# ax.net
KiCad netlist of a schematic drawn in EAGLE
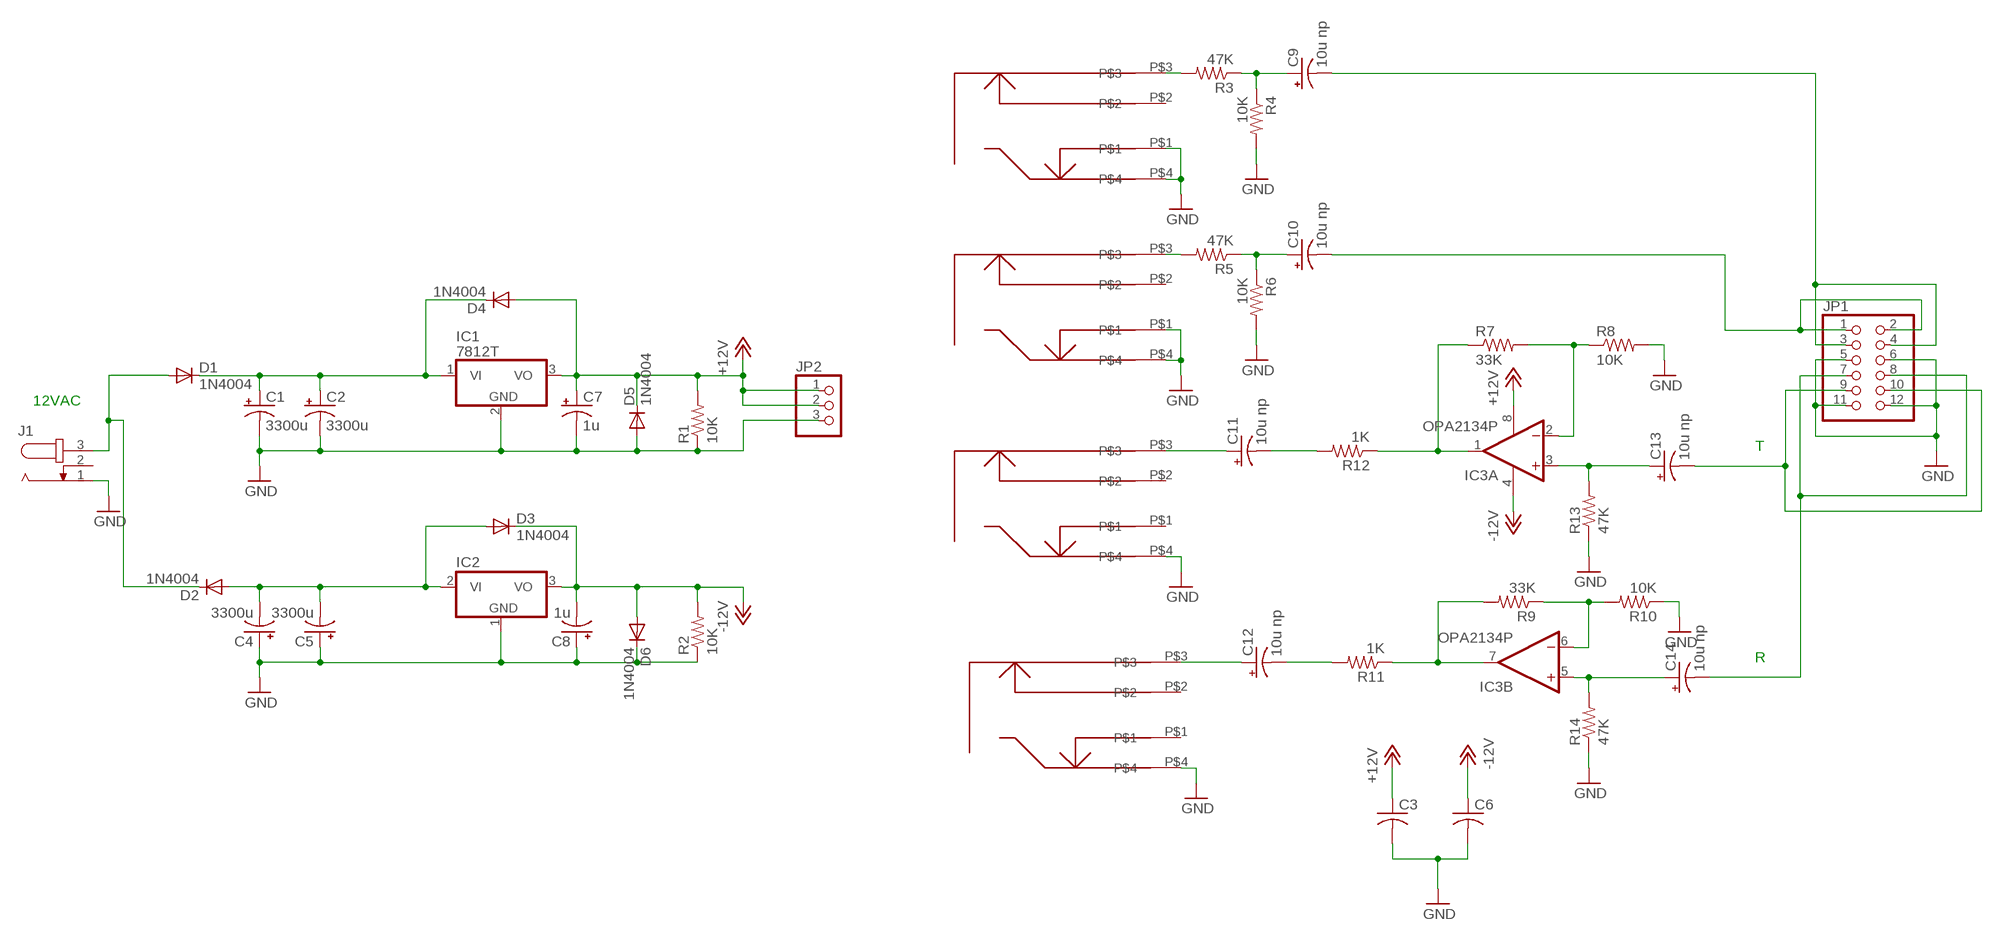
[diagram p0: schematic, sheet 1]

(export (version "E")
  (design (tool "Eeschema 10.0.6"))
  (components
    (comp (ref "C1")
      (value "3300u")
      (footprint "eagle-import:E7,5-18")
      (libsource (lib "eagle-import") (part "CPOL-USE7.5-18"))
    )
    (comp (ref "C2")
      (value "3300u")
      (footprint "eagle-import:E7,5-18")
      (libsource (lib "eagle-import") (part "CPOL-USE7.5-18"))
    )
    (comp (ref "C3")
      (value "C-US050-030X075")
      (footprint "eagle-import:C050-030X075")
      (libsource (lib "eagle-import") (part "C-US050-030X075"))
    )
    (comp (ref "C4")
      (value "3300u")
      (footprint "eagle-import:E7,5-18")
      (libsource (lib "eagle-import") (part "CPOL-USE7.5-18"))
    )
    (comp (ref "C5")
      (value "3300u")
      (footprint "eagle-import:E7,5-18")
      (libsource (lib "eagle-import") (part "CPOL-USE7.5-18"))
    )
    (comp (ref "C6")
      (value "C-US050-030X075")
      (footprint "eagle-import:C050-030X075")
      (libsource (lib "eagle-import") (part "C-US050-030X075"))
    )
    (comp (ref "C7")
      (value "1u")
      (footprint "eagle-import:E2-5")
      (libsource (lib "eagle-import") (part "CPOL-USE2-5"))
    )
    (comp (ref "C8")
      (value "1u")
      (footprint "eagle-import:E2-5")
      (libsource (lib "eagle-import") (part "CPOL-USE2-5"))
    )
    (comp (ref "C9")
      (value "10u np")
      (footprint "eagle-import:E2-5")
      (libsource (lib "eagle-import") (part "CPOL-USE2-5"))
    )
    (comp (ref "C10")
      (value "10u np")
      (footprint "eagle-import:E2-5")
      (libsource (lib "eagle-import") (part "CPOL-USE2-5"))
    )
    (comp (ref "C11")
      (value "10u np")
      (footprint "eagle-import:E2-5")
      (libsource (lib "eagle-import") (part "CPOL-USE2-5"))
    )
    (comp (ref "C12")
      (value "10u np")
      (footprint "eagle-import:E2-5")
      (libsource (lib "eagle-import") (part "CPOL-USE2-5"))
    )
    (comp (ref "C13")
      (value "10u np")
      (footprint "eagle-import:E2-5")
      (libsource (lib "eagle-import") (part "CPOL-USE2-5"))
    )
    (comp (ref "C14")
      (value "10u np")
      (footprint "eagle-import:E2-5")
      (libsource (lib "eagle-import") (part "CPOL-USE2-5"))
    )
    (comp (ref "D1")
      (value "1N4004")
      (footprint "eagle-import:DO41-10")
      (libsource (lib "eagle-import") (part "1N4004"))
    )
    (comp (ref "D2")
      (value "1N4004")
      (footprint "eagle-import:DO41-10")
      (libsource (lib "eagle-import") (part "1N4004"))
    )
    (comp (ref "D3")
      (value "1N4004")
      (footprint "eagle-import:DO41-10")
      (libsource (lib "eagle-import") (part "1N4004"))
    )
    (comp (ref "D4")
      (value "1N4004")
      (footprint "eagle-import:DO41-10")
      (libsource (lib "eagle-import") (part "1N4004"))
    )
    (comp (ref "D5")
      (value "1N4004")
      (footprint "eagle-import:DO41-10")
      (libsource (lib "eagle-import") (part "1N4004"))
    )
    (comp (ref "D6")
      (value "1N4004")
      (footprint "eagle-import:DO41-10")
      (libsource (lib "eagle-import") (part "1N4004"))
    )
    (comp (ref "IC1")
      (value "7812T")
      (footprint "eagle-import:TO220H")
      (libsource (lib "eagle-import") (part "78T12"))
    )
    (comp (ref "IC2")
      (value "7906T")
      (footprint "eagle-import:TO220H")
      (libsource (lib "eagle-import") (part "79T06"))
    )
    (comp (ref "IC3")
      (value "OPA2134P")
      (footprint "eagle-import:DIL08")
      (libsource (lib "eagle-import") (part "OPA2134P"))
    )
    (comp (ref "INL")
      (value "NMJ4HCD2")
      (footprint "eagle-import:NMJ4HCD2")
      (libsource (lib "eagle-import") (part "NMJ4HCD2"))
    )
    (comp (ref "INR")
      (value "NMJ4HCD2")
      (footprint "eagle-import:NMJ4HCD2")
      (libsource (lib "eagle-import") (part "NMJ4HCD2"))
    )
    (comp (ref "J1")
      (value "JACK-PLUG0")
      (footprint "eagle-import:SPC4077")
      (libsource (lib "eagle-import") (part "JACK-PLUG0"))
    )
    (comp (ref "JP1")
      (value "PINHD-2X6")
      (footprint "eagle-import:2X06")
      (libsource (lib "eagle-import") (part "PINHD-2X6"))
    )
    (comp (ref "JP2")
      (value "PINHD-1X3")
      (footprint "eagle-import:1X03")
      (libsource (lib "eagle-import") (part "PINHD-1X3"))
    )
    (comp (ref "OUTL")
      (value "NMJ4HCD2")
      (footprint "eagle-import:NMJ4HCD2")
      (libsource (lib "eagle-import") (part "NMJ4HCD2"))
    )
    (comp (ref "OUTR")
      (value "NMJ4HCD2")
      (footprint "eagle-import:NMJ4HCD2")
      (libsource (lib "eagle-import") (part "NMJ4HCD2"))
    )
    (comp (ref "R1")
      (value "10K")
      (footprint "eagle-import:0207_7")
      (libsource (lib "eagle-import") (part "R-US_0207/7"))
    )
    (comp (ref "R2")
      (value "10K")
      (footprint "eagle-import:0207_7")
      (libsource (lib "eagle-import") (part "R-US_0207/7"))
    )
    (comp (ref "R3")
      (value "47K")
      (footprint "eagle-import:0207_7")
      (libsource (lib "eagle-import") (part "R-US_0207/7"))
    )
    (comp (ref "R4")
      (value "10K")
      (footprint "eagle-import:0207_7")
      (libsource (lib "eagle-import") (part "R-US_0207/7"))
    )
    (comp (ref "R5")
      (value "47K")
      (footprint "eagle-import:0207_7")
      (libsource (lib "eagle-import") (part "R-US_0207/7"))
    )
    (comp (ref "R6")
      (value "10K")
      (footprint "eagle-import:0207_7")
      (libsource (lib "eagle-import") (part "R-US_0207/7"))
    )
    (comp (ref "R7")
      (value "33K")
      (footprint "eagle-import:0207_7")
      (libsource (lib "eagle-import") (part "R-US_0207/7"))
    )
    (comp (ref "R8")
      (value "10K")
      (footprint "eagle-import:0207_7")
      (libsource (lib "eagle-import") (part "R-US_0207/7"))
    )
    (comp (ref "R9")
      (value "33K")
      (footprint "eagle-import:0207_7")
      (libsource (lib "eagle-import") (part "R-US_0207/7"))
    )
    (comp (ref "R10")
      (value "10K")
      (footprint "eagle-import:0207_7")
      (libsource (lib "eagle-import") (part "R-US_0207/7"))
    )
    (comp (ref "R11")
      (value "1K")
      (footprint "eagle-import:0207_7")
      (libsource (lib "eagle-import") (part "R-US_0207/7"))
    )
    (comp (ref "R12")
      (value "1K")
      (footprint "eagle-import:0207_7")
      (libsource (lib "eagle-import") (part "R-US_0207/7"))
    )
    (comp (ref "R13")
      (value "47K")
      (footprint "eagle-import:0207_7")
      (libsource (lib "eagle-import") (part "R-US_0207/7"))
    )
    (comp (ref "R14")
      (value "47K")
      (footprint "eagle-import:0207_7")
      (libsource (lib "eagle-import") (part "R-US_0207/7"))
    )
  )
  (nets
    (net (code "1") (name "+12V") (class "Default")
      (node (ref "C3") (pin "1") (pinfunction "1_1") (pintype "passive"))
      (node (ref "C7") (pin "+") (pinfunction "+_+") (pintype "passive"))
      (node (ref "D4") (pin "A") (pinfunction "A_A") (pintype "passive"))
      (node (ref "D5") (pin "C") (pinfunction "C_C") (pintype "passive"))
      (node (ref "IC1") (pin "3") (pinfunction "VO_3") (pintype "passive"))
      (node (ref "IC3") (pin "8") (pinfunction "V+_8") (pintype "power_in"))
      (node (ref "JP2") (pin "1") (pinfunction "1_1") (pintype "passive"))
      (node (ref "JP2") (pin "2") (pinfunction "2_2") (pintype "passive"))
      (node (ref "R1") (pin "2") (pinfunction "2_2") (pintype "passive"))
    )
    (net (code "2") (name "-12V") (class "Default")
      (node (ref "C6") (pin "1") (pinfunction "1_1") (pintype "passive"))
      (node (ref "C8") (pin "-") (pinfunction "-_-") (pintype "passive"))
      (node (ref "D3") (pin "C") (pinfunction "C_C") (pintype "passive"))
      (node (ref "D6") (pin "A") (pinfunction "A_A") (pintype "passive"))
      (node (ref "IC2") (pin "3") (pinfunction "VO_3") (pintype "passive"))
      (node (ref "IC3") (pin "4") (pinfunction "V-_4") (pintype "power_in"))
      (node (ref "R2") (pin "2") (pinfunction "2_2") (pintype "passive"))
    )
    (net (code "3") (name "GND") (class "Default")
      (node (ref "C1") (pin "-") (pinfunction "-_-") (pintype "passive"))
      (node (ref "C2") (pin "-") (pinfunction "-_-") (pintype "passive"))
      (node (ref "C3") (pin "2") (pinfunction "2_2") (pintype "passive"))
      (node (ref "C4") (pin "+") (pinfunction "+_+") (pintype "passive"))
      (node (ref "C5") (pin "+") (pinfunction "+_+") (pintype "passive"))
      (node (ref "C6") (pin "2") (pinfunction "2_2") (pintype "passive"))
      (node (ref "C7") (pin "-") (pinfunction "-_-") (pintype "passive"))
      (node (ref "C8") (pin "+") (pinfunction "+_+") (pintype "passive"))
      (node (ref "D5") (pin "A") (pinfunction "A_A") (pintype "passive"))
      (node (ref "D6") (pin "C") (pinfunction "C_C") (pintype "passive"))
      (node (ref "IC1") (pin "2") (pinfunction "GND_2") (pintype "passive"))
      (node (ref "IC2") (pin "1") (pinfunction "GND_1") (pintype "passive"))
      (node (ref "INL") (pin "P$1") (pinfunction "P$1_P$1") (pintype "bidirectional"))
      (node (ref "INL") (pin "P$4") (pinfunction "P$4_P$4") (pintype "bidirectional"))
      (node (ref "INR") (pin "P$1") (pinfunction "P$1_P$1") (pintype "bidirectional"))
      (node (ref "INR") (pin "P$4") (pinfunction "P$4_P$4") (pintype "bidirectional"))
      (node (ref "J1") (pin "1") (pinfunction "1_1") (pintype "passive"))
      (node (ref "JP1") (pin "11") (pinfunction "11_11") (pintype "passive"))
      (node (ref "JP1") (pin "12") (pinfunction "12_12") (pintype "passive"))
      (node (ref "JP1") (pin "5") (pinfunction "5_5") (pintype "passive"))
      (node (ref "JP1") (pin "6") (pinfunction "6_6") (pintype "passive"))
      (node (ref "JP2") (pin "3") (pinfunction "3_3") (pintype "passive"))
      (node (ref "OUTL") (pin "P$4") (pinfunction "P$4_P$4") (pintype "bidirectional"))
      (node (ref "OUTR") (pin "P$4") (pinfunction "P$4_P$4") (pintype "bidirectional"))
      (node (ref "R1") (pin "1") (pinfunction "1_1") (pintype "passive"))
      (node (ref "R10") (pin "1") (pinfunction "1_1") (pintype "passive"))
      (node (ref "R13") (pin "1") (pinfunction "1_1") (pintype "passive"))
      (node (ref "R14") (pin "1") (pinfunction "1_1") (pintype "passive"))
      (node (ref "R2") (pin "1") (pinfunction "1_1") (pintype "passive"))
      (node (ref "R4") (pin "2") (pinfunction "2_2") (pintype "passive"))
      (node (ref "R6") (pin "2") (pinfunction "2_2") (pintype "passive"))
      (node (ref "R8") (pin "2") (pinfunction "2_2") (pintype "passive"))
    )
    (net (code "4") (name "Net-(C9-Pad+)") (class "Default")
      (node (ref "C9") (pin "+") (pinfunction "+_+") (pintype "passive"))
      (node (ref "R3") (pin "1") (pinfunction "1_1") (pintype "passive"))
      (node (ref "R4") (pin "1") (pinfunction "1_1") (pintype "passive"))
    )
    (net (code "5") (name "Net-(C9-Pad-)") (class "Default")
      (node (ref "C9") (pin "-") (pinfunction "-_-") (pintype "passive"))
      (node (ref "JP1") (pin "3") (pinfunction "3_3") (pintype "passive"))
      (node (ref "JP1") (pin "4") (pinfunction "4_4") (pintype "passive"))
    )
    (net (code "6") (name "Net-(C10-Pad+)") (class "Default")
      (node (ref "C10") (pin "+") (pinfunction "+_+") (pintype "passive"))
      (node (ref "R5") (pin "1") (pinfunction "1_1") (pintype "passive"))
      (node (ref "R6") (pin "1") (pinfunction "1_1") (pintype "passive"))
    )
    (net (code "7") (name "Net-(C10-Pad-)") (class "Default")
      (node (ref "C10") (pin "-") (pinfunction "-_-") (pintype "passive"))
      (node (ref "JP1") (pin "1") (pinfunction "1_1") (pintype "passive"))
      (node (ref "JP1") (pin "2") (pinfunction "2_2") (pintype "passive"))
    )
    (net (code "8") (name "Net-(C11-Pad+)") (class "Default")
      (node (ref "C11") (pin "+") (pinfunction "+_+") (pintype "passive"))
      (node (ref "OUTL") (pin "P$3") (pinfunction "P$3_P$3") (pintype "bidirectional"))
    )
    (net (code "9") (name "Net-(C11-Pad-)") (class "Default")
      (node (ref "C11") (pin "-") (pinfunction "-_-") (pintype "passive"))
      (node (ref "R12") (pin "2") (pinfunction "2_2") (pintype "passive"))
    )
    (net (code "10") (name "Net-(C12-Pad+)") (class "Default")
      (node (ref "C12") (pin "+") (pinfunction "+_+") (pintype "passive"))
      (node (ref "OUTR") (pin "P$3") (pinfunction "P$3_P$3") (pintype "bidirectional"))
    )
    (net (code "11") (name "Net-(C12-Pad-)") (class "Default")
      (node (ref "C12") (pin "-") (pinfunction "-_-") (pintype "passive"))
      (node (ref "R11") (pin "2") (pinfunction "2_2") (pintype "passive"))
    )
    (net (code "12") (name "Net-(C13-Pad-)") (class "Default")
      (node (ref "C13") (pin "-") (pinfunction "-_-") (pintype "passive"))
      (node (ref "JP1") (pin "10") (pinfunction "10_10") (pintype "passive"))
      (node (ref "JP1") (pin "9") (pinfunction "9_9") (pintype "passive"))
    )
    (net (code "13") (name "Net-(C14-Pad-)") (class "Default")
      (node (ref "C14") (pin "-") (pinfunction "-_-") (pintype "passive"))
      (node (ref "JP1") (pin "7") (pinfunction "7_7") (pintype "passive"))
      (node (ref "JP1") (pin "8") (pinfunction "8_8") (pintype "passive"))
    )
    (net (code "14") (name "Net-(D1-PadA)") (class "Default")
      (node (ref "D1") (pin "A") (pinfunction "A_A") (pintype "passive"))
      (node (ref "D2") (pin "C") (pinfunction "C_C") (pintype "passive"))
      (node (ref "J1") (pin "3") (pinfunction "3_3") (pintype "passive"))
    )
    (net (code "15") (name "Net-(IC1-VI)") (class "Default")
      (node (ref "C1") (pin "+") (pinfunction "+_+") (pintype "passive"))
      (node (ref "C2") (pin "+") (pinfunction "+_+") (pintype "passive"))
      (node (ref "D1") (pin "C") (pinfunction "C_C") (pintype "passive"))
      (node (ref "D4") (pin "C") (pinfunction "C_C") (pintype "passive"))
      (node (ref "IC1") (pin "1") (pinfunction "VI_1") (pintype "input"))
    )
    (net (code "16") (name "Net-(IC2-VI)") (class "Default")
      (node (ref "C4") (pin "-") (pinfunction "-_-") (pintype "passive"))
      (node (ref "C5") (pin "-") (pinfunction "-_-") (pintype "passive"))
      (node (ref "D2") (pin "A") (pinfunction "A_A") (pintype "passive"))
      (node (ref "D3") (pin "A") (pinfunction "A_A") (pintype "passive"))
      (node (ref "IC2") (pin "2") (pinfunction "VI_2") (pintype "input"))
    )
    (net (code "17") (name "Net-(IC3A-+IN)") (class "Default")
      (node (ref "C13") (pin "+") (pinfunction "+_+") (pintype "passive"))
      (node (ref "IC3") (pin "3") (pinfunction "+IN_3") (pintype "input"))
      (node (ref "R13") (pin "2") (pinfunction "2_2") (pintype "passive"))
    )
    (net (code "18") (name "Net-(IC3A--IN)") (class "Default")
      (node (ref "IC3") (pin "2") (pinfunction "-IN_2") (pintype "input"))
      (node (ref "R7") (pin "2") (pinfunction "2_2") (pintype "passive"))
      (node (ref "R8") (pin "1") (pinfunction "1_1") (pintype "passive"))
    )
    (net (code "19") (name "Net-(IC3A-OUT)") (class "Default")
      (node (ref "IC3") (pin "1") (pinfunction "OUT_1") (pintype "output"))
      (node (ref "R12") (pin "1") (pinfunction "1_1") (pintype "passive"))
      (node (ref "R7") (pin "1") (pinfunction "1_1") (pintype "passive"))
    )
    (net (code "20") (name "Net-(IC3B-+IN)") (class "Default")
      (node (ref "C14") (pin "+") (pinfunction "+_+") (pintype "passive"))
      (node (ref "IC3") (pin "5") (pinfunction "+IN_5") (pintype "input"))
      (node (ref "R14") (pin "2") (pinfunction "2_2") (pintype "passive"))
    )
    (net (code "21") (name "Net-(IC3B--IN)") (class "Default")
      (node (ref "IC3") (pin "6") (pinfunction "-IN_6") (pintype "input"))
      (node (ref "R10") (pin "2") (pinfunction "2_2") (pintype "passive"))
      (node (ref "R9") (pin "1") (pinfunction "1_1") (pintype "passive"))
    )
    (net (code "22") (name "Net-(IC3B-OUT)") (class "Default")
      (node (ref "IC3") (pin "7") (pinfunction "OUT_7") (pintype "output"))
      (node (ref "R11") (pin "1") (pinfunction "1_1") (pintype "passive"))
      (node (ref "R9") (pin "2") (pinfunction "2_2") (pintype "passive"))
    )
    (net (code "23") (name "Net-(INL-PadP$3)") (class "Default")
      (node (ref "INL") (pin "P$3") (pinfunction "P$3_P$3") (pintype "bidirectional"))
      (node (ref "R3") (pin "2") (pinfunction "2_2") (pintype "passive"))
    )
    (net (code "24") (name "Net-(INR-PadP$3)") (class "Default")
      (node (ref "INR") (pin "P$3") (pinfunction "P$3_P$3") (pintype "bidirectional"))
      (node (ref "R5") (pin "2") (pinfunction "2_2") (pintype "passive"))
    )
    (net (code "25") (name "unconnected-(INL-PadP$2)") (class "Default")
      (node (ref "INL") (pin "P$2") (pinfunction "P$2_P$2") (pintype "bidirectional"))
    )
    (net (code "26") (name "unconnected-(INR-PadP$2)") (class "Default")
      (node (ref "INR") (pin "P$2") (pinfunction "P$2_P$2") (pintype "bidirectional"))
    )
    (net (code "27") (name "unconnected-(J1-Pad2)") (class "Default")
      (node (ref "J1") (pin "2") (pinfunction "2_2") (pintype "passive"))
    )
    (net (code "28") (name "unconnected-(OUTL-PadP$1)") (class "Default")
      (node (ref "OUTL") (pin "P$1") (pinfunction "P$1_P$1") (pintype "bidirectional"))
    )
    (net (code "29") (name "unconnected-(OUTL-PadP$2)") (class "Default")
      (node (ref "OUTL") (pin "P$2") (pinfunction "P$2_P$2") (pintype "bidirectional"))
    )
    (net (code "30") (name "unconnected-(OUTR-PadP$1)") (class "Default")
      (node (ref "OUTR") (pin "P$1") (pinfunction "P$1_P$1") (pintype "bidirectional"))
    )
    (net (code "31") (name "unconnected-(OUTR-PadP$2)") (class "Default")
      (node (ref "OUTR") (pin "P$2") (pinfunction "P$2_P$2") (pintype "bidirectional"))
    )
  )
)
